# Sch.net
KiCad netlist of a schematic drawn in EAGLE
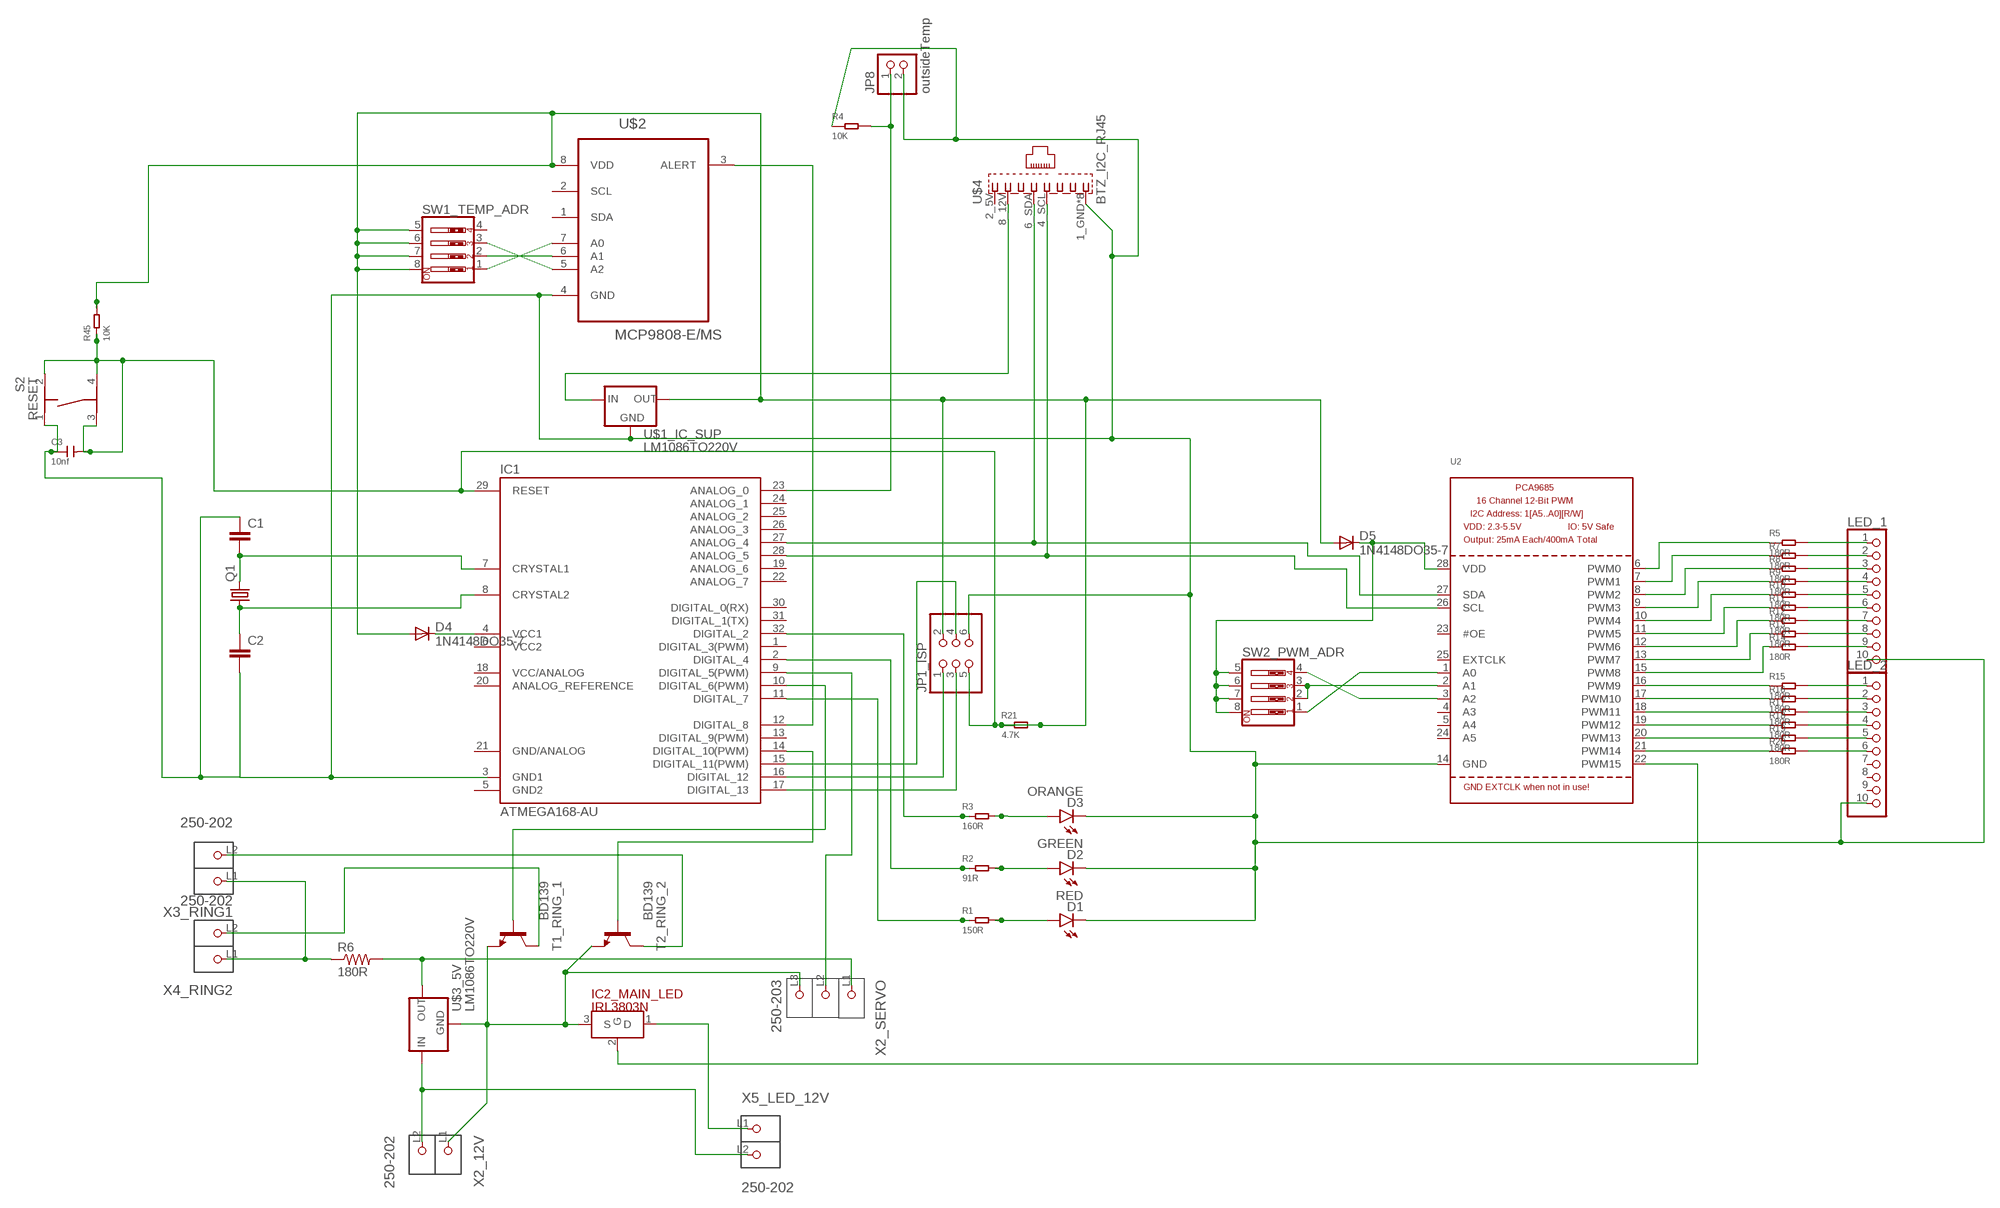
[diagram p0: schematic, sheet 1]

(export (version "E")
  (design (tool "Eeschema 10.0.6"))
  (components
    (comp (ref "C1")
      (value "C-EU025-025X050")
      (footprint "eagle-import:C025-025X050")
      (libsource (lib "eagle-import") (part "C-EU025-025X050"))
    )
    (comp (ref "C2")
      (value "C-EU025-025X050")
      (footprint "eagle-import:C025-025X050")
      (libsource (lib "eagle-import") (part "C-EU025-025X050"))
    )
    (comp (ref "C3")
      (value "10nf")
      (footprint "eagle-import:C0603")
      (fields (field (name "MPN") "CC0603KRX7R9BB103"))
      (libsource (lib "eagle-import") (part "CERAMIC-10NF-50V-10%-X7R(0603)"))
    )
    (comp (ref "D1")
      (value "RED")
      (footprint "eagle-import:LED-0603")
      (libsource (lib "eagle-import") (part "LED-RED0603"))
    )
    (comp (ref "D2")
      (value "GREEN")
      (footprint "eagle-import:LED-0603")
      (libsource (lib "eagle-import") (part "LED-RED0603"))
    )
    (comp (ref "D3")
      (value "ORANGE")
      (footprint "eagle-import:LED-0603")
      (libsource (lib "eagle-import") (part "LED-RED0603"))
    )
    (comp (ref "D4")
      (value "1N4148DO35-7")
      (footprint "eagle-import:DO35-7")
      (libsource (lib "eagle-import") (part "1N4148DO35-7"))
    )
    (comp (ref "D5")
      (value "1N4148DO35-7")
      (footprint "eagle-import:DO35-7")
      (libsource (lib "eagle-import") (part "1N4148DO35-7"))
    )
    (comp (ref "IC1")
      (value "ATMEGA168-AU")
      (footprint "eagle-import:TQFP32-08")
      (libsource (lib "eagle-import") (part "ATMEGA168-AU"))
    )
    (comp (ref "IC2_MAIN_LED")
      (value "IRL3803N")
      (footprint "eagle-import:TO220")
      (libsource (lib "eagle-import") (part "IRL3803N"))
    )
    (comp (ref "JP1_ISP")
      (value "PINHD-2X3")
      (footprint "eagle-import:2X03")
      (libsource (lib "eagle-import") (part "PINHD-2X3"))
    )
    (comp (ref "JP8")
      (value "outsideTemp")
      (footprint "eagle-import:1X02")
      (libsource (lib "eagle-import") (part "PINHD-1X2"))
    )
    (comp (ref "LED_1")
      (value "PINHD-1X10")
      (footprint "eagle-import:1X10")
      (libsource (lib "eagle-import") (part "PINHD-1X10"))
    )
    (comp (ref "LED_2")
      (value "PINHD-1X10")
      (footprint "eagle-import:1X10")
      (libsource (lib "eagle-import") (part "PINHD-1X10"))
    )
    (comp (ref "Q1")
      (value "CRYSTALHC49S")
      (footprint "eagle-import:HC49_S")
      (libsource (lib "eagle-import") (part "CRYSTALHC49S"))
    )
    (comp (ref "R1")
      (value "150R")
      (footprint "eagle-import:R0603")
      (fields (field (name "MPN") "RC0603JR-07100RL"))
      (libsource (lib "eagle-import") (part "SMD-RES-100R-5%-1/10W(0603)"))
    )
    (comp (ref "R2")
      (value "91R")
      (footprint "eagle-import:R0603")
      (fields (field (name "MPN") "RC0603JR-07100RL"))
      (libsource (lib "eagle-import") (part "SMD-RES-100R-5%-1/10W(0603)"))
    )
    (comp (ref "R3")
      (value "160R")
      (footprint "eagle-import:R0603")
      (fields (field (name "MPN") "RC0603JR-07100RL"))
      (libsource (lib "eagle-import") (part "SMD-RES-100R-5%-1/10W(0603)"))
    )
    (comp (ref "R4")
      (value "10K")
      (footprint "eagle-import:R0603")
      (fields (field (name "MPN") "RC0603FR-0710KL"))
      (libsource (lib "eagle-import") (part "SMD-RES-10K-1%-1/10W(0603)"))
    )
    (comp (ref "R5")
      (value "180R")
      (footprint "eagle-import:R0603")
      (fields (field (name "MPN") "RC0603JR-07100RL"))
      (libsource (lib "eagle-import") (part "SMD-RES-100R-5%-1/10W(0603)"))
    )
    (comp (ref "R6")
      (value "180R")
      (footprint "eagle-import:0805-THM")
      (libsource (lib "eagle-import") (part "FLIPFLOP-RES"))
    )
    (comp (ref "R7")
      (value "180R")
      (footprint "eagle-import:R0603")
      (fields (field (name "MPN") "RC0603JR-07100RL"))
      (libsource (lib "eagle-import") (part "SMD-RES-100R-5%-1/10W(0603)"))
    )
    (comp (ref "R8")
      (value "180R")
      (footprint "eagle-import:R0603")
      (fields (field (name "MPN") "RC0603JR-07100RL"))
      (libsource (lib "eagle-import") (part "SMD-RES-100R-5%-1/10W(0603)"))
    )
    (comp (ref "R9")
      (value "180R")
      (footprint "eagle-import:R0603")
      (fields (field (name "MPN") "RC0603JR-07100RL"))
      (libsource (lib "eagle-import") (part "SMD-RES-100R-5%-1/10W(0603)"))
    )
    (comp (ref "R10")
      (value "180R")
      (footprint "eagle-import:R0603")
      (fields (field (name "MPN") "RC0603JR-07100RL"))
      (libsource (lib "eagle-import") (part "SMD-RES-100R-5%-1/10W(0603)"))
    )
    (comp (ref "R11")
      (value "180R")
      (footprint "eagle-import:R0603")
      (fields (field (name "MPN") "RC0603JR-07100RL"))
      (libsource (lib "eagle-import") (part "SMD-RES-100R-5%-1/10W(0603)"))
    )
    (comp (ref "R12")
      (value "180R")
      (footprint "eagle-import:R0603")
      (fields (field (name "MPN") "RC0603JR-07100RL"))
      (libsource (lib "eagle-import") (part "SMD-RES-100R-5%-1/10W(0603)"))
    )
    (comp (ref "R13")
      (value "180R")
      (footprint "eagle-import:R0603")
      (fields (field (name "MPN") "RC0603JR-07100RL"))
      (libsource (lib "eagle-import") (part "SMD-RES-100R-5%-1/10W(0603)"))
    )
    (comp (ref "R14")
      (value "180R")
      (footprint "eagle-import:R0603")
      (fields (field (name "MPN") "RC0603JR-07100RL"))
      (libsource (lib "eagle-import") (part "SMD-RES-100R-5%-1/10W(0603)"))
    )
    (comp (ref "R15")
      (value "180R")
      (footprint "eagle-import:R0603")
      (fields (field (name "MPN") "RC0603JR-07100RL"))
      (libsource (lib "eagle-import") (part "SMD-RES-100R-5%-1/10W(0603)"))
    )
    (comp (ref "R16")
      (value "180R")
      (footprint "eagle-import:R0603")
      (fields (field (name "MPN") "RC0603JR-07100RL"))
      (libsource (lib "eagle-import") (part "SMD-RES-100R-5%-1/10W(0603)"))
    )
    (comp (ref "R17")
      (value "180R")
      (footprint "eagle-import:R0603")
      (fields (field (name "MPN") "RC0603JR-07100RL"))
      (libsource (lib "eagle-import") (part "SMD-RES-100R-5%-1/10W(0603)"))
    )
    (comp (ref "R18")
      (value "180R")
      (footprint "eagle-import:R0603")
      (fields (field (name "MPN") "RC0603JR-07100RL"))
      (libsource (lib "eagle-import") (part "SMD-RES-100R-5%-1/10W(0603)"))
    )
    (comp (ref "R19")
      (value "180R")
      (footprint "eagle-import:R0603")
      (fields (field (name "MPN") "RC0603JR-07100RL"))
      (libsource (lib "eagle-import") (part "SMD-RES-100R-5%-1/10W(0603)"))
    )
    (comp (ref "R20")
      (value "180R")
      (footprint "eagle-import:R0603")
      (fields (field (name "MPN") "RC0603JR-07100RL"))
      (libsource (lib "eagle-import") (part "SMD-RES-100R-5%-1/10W(0603)"))
    )
    (comp (ref "R21")
      (value "4.7K")
      (footprint "eagle-import:R0603")
      (fields (field (name "MPN") "RC0603JR-074K7L"))
      (libsource (lib "eagle-import") (part "SMD-RES-4.7K-5%-1/10W(0603)"))
    )
    (comp (ref "R45")
      (value "10K")
      (footprint "eagle-import:R0603")
      (fields (field (name "MPN") "RC0603FR-0710KL"))
      (libsource (lib "eagle-import") (part "SMD-RES-10K-1%-1/10W(0603)"))
    )
    (comp (ref "S2")
      (value "RESET")
      (footprint "eagle-import:TASTER-9314_SMD")
      (libsource (lib "eagle-import") (part "TASTER-9314_SMD"))
    )
    (comp (ref "SW1_TEMP_ADR")
      (value "SW_DIP-4")
      (footprint "eagle-import:EDG-04")
      (libsource (lib "eagle-import") (part "SW_DIP-4"))
    )
    (comp (ref "SW2_PWM_ADR")
      (value "SW_DIP-4")
      (footprint "eagle-import:EDG-04")
      (libsource (lib "eagle-import") (part "SW_DIP-4"))
    )
    (comp (ref "T1_RING_1")
      (value "BD139")
      (footprint "eagle-import:TO126")
      (libsource (lib "eagle-import") (part "BD139"))
    )
    (comp (ref "T2_RING_2")
      (value "BD139")
      (footprint "eagle-import:TO126")
      (libsource (lib "eagle-import") (part "BD139"))
    )
    (comp (ref "U$1_IC_SUP")
      (value "LM1086TO220V")
      (footprint "eagle-import:TO220S")
      (libsource (lib "eagle-import") (part "LM1086TO220V"))
    )
    (comp (ref "U$2")
      (value "MCP9808-E/MS")
      (footprint "eagle-import:SOP65P490X110-8N")
      (libsource (lib "eagle-import") (part "MCP9808-E/MS"))
    )
    (comp (ref "U$3_5V")
      (value "LM1086TO220V")
      (footprint "eagle-import:TO220S")
      (libsource (lib "eagle-import") (part "LM1086TO220V"))
    )
    (comp (ref "U$4")
      (value "BTZ_I2C_RJ45")
      (footprint "eagle-import:RJ45")
      (libsource (lib "eagle-import") (part "BTZ_I2C_RJ45"))
    )
    (comp (ref "U2")
      (value "PCA9685")
      (footprint "eagle-import:TSSOP28")
      (libsource (lib "eagle-import") (part "PCA9685"))
    )
    (comp (ref "X2_12V")
      (value "250-202")
      (footprint "eagle-import:P-250-202")
      (libsource (lib "eagle-import") (part "250-202"))
    )
    (comp (ref "X2_SERVO")
      (value "250-203")
      (footprint "eagle-import:P-250-203")
      (libsource (lib "eagle-import") (part "250-203"))
    )
    (comp (ref "X3_RING1")
      (value "250-202")
      (footprint "eagle-import:P-250-202")
      (libsource (lib "eagle-import") (part "250-202"))
    )
    (comp (ref "X4_RING2")
      (value "250-202")
      (footprint "eagle-import:P-250-202")
      (libsource (lib "eagle-import") (part "250-202"))
    )
    (comp (ref "X5_LED_12V")
      (value "250-202")
      (footprint "eagle-import:P-250-202")
      (libsource (lib "eagle-import") (part "250-202"))
    )
  )
  (nets
    (net (code "1") (name "/GND1") (class "Default")
      (node (ref "IC1") (pin "3") (pinfunction "GND1_3") (pintype "power_in"))
    )
    (net (code "2") (name "/GND2") (class "Default")
      (node (ref "IC1") (pin "5") (pinfunction "GND2_5") (pintype "power_in"))
    )
    (net (code "3") (name "/GND{slash}ANALOG") (class "Default")
      (node (ref "IC1") (pin "21") (pinfunction "GND/ANALOG_21") (pintype "power_in"))
    )
    (net (code "4") (name "/VCC2") (class "Default")
      (node (ref "IC1") (pin "6") (pinfunction "VCC2_6") (pintype "power_in"))
    )
    (net (code "5") (name "Net-(D1-PadA)") (class "Default")
      (node (ref "D1") (pin "A") (pinfunction "A_A") (pintype "passive"))
      (node (ref "R1") (pin "2") (pinfunction "2_2") (pintype "passive"))
    )
    (net (code "6") (name "Net-(D2-PadA)") (class "Default")
      (node (ref "D2") (pin "A") (pinfunction "A_A") (pintype "passive"))
      (node (ref "R2") (pin "2") (pinfunction "2_2") (pintype "passive"))
    )
    (net (code "7") (name "Net-(D3-PadA)") (class "Default")
      (node (ref "D3") (pin "A") (pinfunction "A_A") (pintype "passive"))
      (node (ref "R3") (pin "2") (pinfunction "2_2") (pintype "passive"))
    )
    (net (code "8") (name "Net-(IC1-ANALOG_0)") (class "Default")
      (node (ref "IC1") (pin "23") (pinfunction "ANALOG_0_23") (pintype "bidirectional"))
      (node (ref "JP8") (pin "1") (pinfunction "1_1") (pintype "passive"))
      (node (ref "R4") (pin "2") (pinfunction "2_2") (pintype "passive"))
    )
    (net (code "9") (name "Net-(IC1-ANALOG_4)") (class "Default")
      (node (ref "IC1") (pin "27") (pinfunction "ANALOG_4_27") (pintype "bidirectional"))
      (node (ref "U$4") (pin "6_SDA") (pinfunction "SDA_6_SDA") (pintype "passive"))
      (node (ref "U2") (pin "27") (pinfunction "SDA_27") (pintype "bidirectional"))
    )
    (net (code "10") (name "Net-(IC1-ANALOG_5)") (class "Default")
      (node (ref "IC1") (pin "28") (pinfunction "ANALOG_5_28") (pintype "bidirectional"))
      (node (ref "U$4") (pin "4_SCL") (pinfunction "SCL_4_SCL") (pintype "passive"))
      (node (ref "U2") (pin "26") (pinfunction "SCL_26") (pintype "bidirectional"))
    )
    (net (code "11") (name "Net-(IC1-CRYSTAL1)") (class "Default")
      (node (ref "C1") (pin "2") (pinfunction "2_2") (pintype "passive"))
      (node (ref "IC1") (pin "7") (pinfunction "CRYSTAL1_7") (pintype "bidirectional"))
      (node (ref "Q1") (pin "2") (pinfunction "2_2") (pintype "passive"))
    )
    (net (code "12") (name "Net-(IC1-CRYSTAL2)") (class "Default")
      (node (ref "C2") (pin "1") (pinfunction "1_1") (pintype "passive"))
      (node (ref "IC1") (pin "8") (pinfunction "CRYSTAL2_8") (pintype "bidirectional"))
      (node (ref "Q1") (pin "1") (pinfunction "1_1") (pintype "passive"))
    )
    (net (code "13") (name "Net-(IC1-DIGITAL_2)") (class "Default")
      (node (ref "IC1") (pin "32") (pinfunction "DIGITAL_2_32") (pintype "bidirectional"))
      (node (ref "R3") (pin "1") (pinfunction "1_1") (pintype "passive"))
    )
    (net (code "14") (name "Net-(IC1-DIGITAL_4)") (class "Default")
      (node (ref "IC1") (pin "2") (pinfunction "DIGITAL_4_2") (pintype "bidirectional"))
      (node (ref "R2") (pin "1") (pinfunction "1_1") (pintype "passive"))
    )
    (net (code "15") (name "Net-(IC1-DIGITAL_5(PWM))") (class "Default")
      (node (ref "IC1") (pin "9") (pinfunction "DIGITAL_5(PWM)_9") (pintype "bidirectional"))
      (node (ref "X2_SERVO") (pin "L2") (pinfunction "P2_L2") (pintype "bidirectional"))
    )
    (net (code "16") (name "Net-(IC1-DIGITAL_6(PWM))") (class "Default")
      (node (ref "IC1") (pin "10") (pinfunction "DIGITAL_6(PWM)_10") (pintype "bidirectional"))
      (node (ref "T1_RING_1") (pin "3") (pinfunction "B_3") (pintype "passive"))
    )
    (net (code "17") (name "Net-(IC1-DIGITAL_7)") (class "Default")
      (node (ref "IC1") (pin "11") (pinfunction "DIGITAL_7_11") (pintype "bidirectional"))
      (node (ref "R1") (pin "1") (pinfunction "1_1") (pintype "passive"))
    )
    (net (code "18") (name "Net-(IC1-DIGITAL_8)") (class "Default")
      (node (ref "IC1") (pin "12") (pinfunction "DIGITAL_8_12") (pintype "bidirectional"))
      (node (ref "U$2") (pin "3") (pinfunction "ALERT_3") (pintype "output"))
    )
    (net (code "19") (name "Net-(IC1-DIGITAL_10(PWM))") (class "Default")
      (node (ref "IC1") (pin "14") (pinfunction "DIGITAL_10(PWM)_14") (pintype "bidirectional"))
      (node (ref "T2_RING_2") (pin "3") (pinfunction "B_3") (pintype "passive"))
    )
    (net (code "20") (name "Net-(IC1-DIGITAL_11(PWM))") (class "Default")
      (node (ref "IC1") (pin "15") (pinfunction "DIGITAL_11(PWM)_15") (pintype "bidirectional"))
      (node (ref "JP1_ISP") (pin "4") (pinfunction "4_4") (pintype "passive"))
    )
    (net (code "21") (name "Net-(IC1-DIGITAL_12)") (class "Default")
      (node (ref "IC1") (pin "16") (pinfunction "DIGITAL_12_16") (pintype "bidirectional"))
      (node (ref "JP1_ISP") (pin "1") (pinfunction "1_1") (pintype "passive"))
    )
    (net (code "22") (name "Net-(IC1-DIGITAL_13)") (class "Default")
      (node (ref "IC1") (pin "17") (pinfunction "DIGITAL_13_17") (pintype "bidirectional"))
      (node (ref "JP1_ISP") (pin "3") (pinfunction "3_3") (pintype "passive"))
    )
    (net (code "23") (name "Net-(IC1-RESET)") (class "Default")
      (node (ref "C3") (pin "2") (pinfunction "2_2") (pintype "passive"))
      (node (ref "D4") (pin "A") (pinfunction "A_A") (pintype "passive"))
      (node (ref "D5") (pin "A") (pinfunction "A_A") (pintype "passive"))
      (node (ref "IC1") (pin "29") (pinfunction "RESET_29") (pintype "bidirectional"))
      (node (ref "JP1_ISP") (pin "2") (pinfunction "2_2") (pintype "passive"))
      (node (ref "JP1_ISP") (pin "5") (pinfunction "5_5") (pintype "passive"))
      (node (ref "R21") (pin "1") (pinfunction "1_1") (pintype "passive"))
      (node (ref "R21") (pin "2") (pinfunction "2_2") (pintype "passive"))
      (node (ref "R45") (pin "1") (pinfunction "1_1") (pintype "passive"))
      (node (ref "R45") (pin "2") (pinfunction "2_2") (pintype "passive"))
      (node (ref "S2") (pin "2") (pinfunction "2_2") (pintype "passive"))
      (node (ref "S2") (pin "3") (pinfunction "3_3") (pintype "passive"))
      (node (ref "S2") (pin "4") (pinfunction "4_4") (pintype "passive"))
      (node (ref "SW1_TEMP_ADR") (pin "5") (pinfunction "5_5") (pintype "passive"))
      (node (ref "SW1_TEMP_ADR") (pin "6") (pinfunction "6_6") (pintype "passive"))
      (node (ref "SW1_TEMP_ADR") (pin "7") (pinfunction "7_7") (pintype "passive"))
      (node (ref "SW1_TEMP_ADR") (pin "8") (pinfunction "8_8") (pintype "passive"))
      (node (ref "U$1_IC_SUP") (pin "2") (pinfunction "OUT_2") (pintype "passive"))
      (node (ref "U$2") (pin "8") (pinfunction "VDD_8") (pintype "power_in"))
    )
    (net (code "24") (name "Net-(IC1-VCC1)") (class "Default")
      (node (ref "D4") (pin "C") (pinfunction "C_C") (pintype "passive"))
      (node (ref "IC1") (pin "4") (pinfunction "VCC1_4") (pintype "power_in"))
    )
    (net (code "25") (name "Net-(IC2_MAIN_LED-D)") (class "Default")
      (node (ref "IC2_MAIN_LED") (pin "1") (pinfunction "D_1") (pintype "output"))
      (node (ref "X5_LED_12V") (pin "L1") (pinfunction "P1_L1") (pintype "bidirectional"))
    )
    (net (code "26") (name "Net-(IC2_MAIN_LED-G)") (class "Default")
      (node (ref "IC2_MAIN_LED") (pin "2") (pinfunction "G_2") (pintype "input"))
      (node (ref "U2") (pin "22") (pinfunction "PWM15_22") (pintype "output"))
    )
    (net (code "27") (name "Net-(IC2_MAIN_LED-S)") (class "Default")
      (node (ref "IC2_MAIN_LED") (pin "3") (pinfunction "S_3") (pintype "power_in"))
      (node (ref "T1_RING_1") (pin "1") (pinfunction "E_1") (pintype "passive"))
      (node (ref "T2_RING_2") (pin "1") (pinfunction "E_1") (pintype "passive"))
      (node (ref "U$3_5V") (pin "1") (pinfunction "GND_1") (pintype "input"))
      (node (ref "X2_12V") (pin "L1") (pinfunction "P1_L1") (pintype "bidirectional"))
      (node (ref "X2_SERVO") (pin "L3") (pinfunction "P3_L3") (pintype "bidirectional"))
    )
    (net (code "28") (name "Net-(LED_1-Pad1)") (class "Default")
      (node (ref "LED_1") (pin "1") (pinfunction "1_1") (pintype "passive"))
      (node (ref "R5") (pin "2") (pinfunction "2_2") (pintype "passive"))
    )
    (net (code "29") (name "Net-(LED_1-Pad2)") (class "Default")
      (node (ref "LED_1") (pin "2") (pinfunction "2_2") (pintype "passive"))
      (node (ref "R7") (pin "2") (pinfunction "2_2") (pintype "passive"))
    )
    (net (code "30") (name "Net-(LED_1-Pad3)") (class "Default")
      (node (ref "LED_1") (pin "3") (pinfunction "3_3") (pintype "passive"))
      (node (ref "R8") (pin "2") (pinfunction "2_2") (pintype "passive"))
    )
    (net (code "31") (name "Net-(LED_1-Pad4)") (class "Default")
      (node (ref "LED_1") (pin "4") (pinfunction "4_4") (pintype "passive"))
      (node (ref "R9") (pin "2") (pinfunction "2_2") (pintype "passive"))
    )
    (net (code "32") (name "Net-(LED_1-Pad5)") (class "Default")
      (node (ref "LED_1") (pin "5") (pinfunction "5_5") (pintype "passive"))
      (node (ref "R10") (pin "2") (pinfunction "2_2") (pintype "passive"))
    )
    (net (code "33") (name "Net-(LED_1-Pad6)") (class "Default")
      (node (ref "LED_1") (pin "6") (pinfunction "6_6") (pintype "passive"))
      (node (ref "R11") (pin "2") (pinfunction "2_2") (pintype "passive"))
    )
    (net (code "34") (name "Net-(LED_1-Pad7)") (class "Default")
      (node (ref "LED_1") (pin "7") (pinfunction "7_7") (pintype "passive"))
      (node (ref "R12") (pin "2") (pinfunction "2_2") (pintype "passive"))
    )
    (net (code "35") (name "Net-(LED_1-Pad8)") (class "Default")
      (node (ref "LED_1") (pin "8") (pinfunction "8_8") (pintype "passive"))
      (node (ref "R13") (pin "2") (pinfunction "2_2") (pintype "passive"))
    )
    (net (code "36") (name "Net-(LED_1-Pad9)") (class "Default")
      (node (ref "LED_1") (pin "9") (pinfunction "9_9") (pintype "passive"))
      (node (ref "R14") (pin "2") (pinfunction "2_2") (pintype "passive"))
    )
    (net (code "37") (name "Net-(LED_2-Pad1)") (class "Default")
      (node (ref "LED_2") (pin "1") (pinfunction "1_1") (pintype "passive"))
      (node (ref "R15") (pin "2") (pinfunction "2_2") (pintype "passive"))
    )
    (net (code "38") (name "Net-(LED_2-Pad2)") (class "Default")
      (node (ref "LED_2") (pin "2") (pinfunction "2_2") (pintype "passive"))
      (node (ref "R16") (pin "2") (pinfunction "2_2") (pintype "passive"))
    )
    (net (code "39") (name "Net-(LED_2-Pad3)") (class "Default")
      (node (ref "LED_2") (pin "3") (pinfunction "3_3") (pintype "passive"))
      (node (ref "R17") (pin "2") (pinfunction "2_2") (pintype "passive"))
    )
    (net (code "40") (name "Net-(LED_2-Pad4)") (class "Default")
      (node (ref "LED_2") (pin "4") (pinfunction "4_4") (pintype "passive"))
      (node (ref "R18") (pin "2") (pinfunction "2_2") (pintype "passive"))
    )
    (net (code "41") (name "Net-(LED_2-Pad5)") (class "Default")
      (node (ref "LED_2") (pin "5") (pinfunction "5_5") (pintype "passive"))
      (node (ref "R19") (pin "2") (pinfunction "2_2") (pintype "passive"))
    )
    (net (code "42") (name "Net-(LED_2-Pad6)") (class "Default")
      (node (ref "LED_2") (pin "6") (pinfunction "6_6") (pintype "passive"))
      (node (ref "R20") (pin "2") (pinfunction "2_2") (pintype "passive"))
    )
    (net (code "43") (name "Net-(T1_RING_1-C)") (class "Default")
      (node (ref "T1_RING_1") (pin "2") (pinfunction "C_2") (pintype "passive"))
      (node (ref "X4_RING2") (pin "L2") (pinfunction "P2_L2") (pintype "bidirectional"))
    )
    (net (code "44") (name "Net-(T2_RING_2-C)") (class "Default")
      (node (ref "T2_RING_2") (pin "2") (pinfunction "C_2") (pintype "passive"))
      (node (ref "X3_RING1") (pin "L2") (pinfunction "P2_L2") (pintype "bidirectional"))
    )
    (net (code "45") (name "Net-(U$1_IC_SUP-GND)") (class "Default")
      (node (ref "C1") (pin "1") (pinfunction "1_1") (pintype "passive"))
      (node (ref "C2") (pin "2") (pinfunction "2_2") (pintype "passive"))
      (node (ref "C3") (pin "1") (pinfunction "1_1") (pintype "passive"))
      (node (ref "D1") (pin "C") (pinfunction "C_C") (pintype "passive"))
      (node (ref "D2") (pin "C") (pinfunction "C_C") (pintype "passive"))
      (node (ref "D3") (pin "C") (pinfunction "C_C") (pintype "passive"))
      (node (ref "JP1_ISP") (pin "6") (pinfunction "6_6") (pintype "passive"))
      (node (ref "JP8") (pin "2") (pinfunction "2_2") (pintype "passive"))
      (node (ref "LED_1") (pin "10") (pinfunction "10_10") (pintype "passive"))
      (node (ref "LED_2") (pin "10") (pinfunction "10_10") (pintype "passive"))
      (node (ref "R4") (pin "1") (pinfunction "1_1") (pintype "passive"))
      (node (ref "S2") (pin "1") (pinfunction "1_1") (pintype "passive"))
      (node (ref "U$1_IC_SUP") (pin "1") (pinfunction "GND_1") (pintype "input"))
      (node (ref "U$2") (pin "4") (pinfunction "GND_4") (pintype "passive"))
      (node (ref "U$4") (pin "1_GND") (pinfunction "GND_1_GND") (pintype "passive"))
      (node (ref "U$4") (pin "3_GND") (pinfunction "GND_3_GND") (pintype "passive"))
      (node (ref "U$4") (pin "5_GND") (pinfunction "GND_5_GND") (pintype "passive"))
      (node (ref "U$4") (pin "7_GND") (pinfunction "GND_7_GND") (pintype "passive"))
      (node (ref "U$4") (pin "G1") (pinfunction "GND_G1") (pintype "passive"))
      (node (ref "U$4") (pin "G2") (pinfunction "GND_G2") (pintype "passive"))
      (node (ref "U$4") (pin "G3") (pinfunction "GND_G3") (pintype "passive"))
      (node (ref "U$4") (pin "G4") (pinfunction "GND_G4") (pintype "passive"))
      (node (ref "U2") (pin "14") (pinfunction "GND_14") (pintype "power_in"))
    )
    (net (code "46") (name "Net-(U$1_IC_SUP-IN)") (class "Default")
      (node (ref "U$1_IC_SUP") (pin "3") (pinfunction "IN_3") (pintype "input"))
      (node (ref "U$4") (pin "8_12V") (pinfunction "12V_8_12V") (pintype "passive"))
    )
    (net (code "47") (name "Net-(U$2-A0)") (class "Default")
      (node (ref "SW1_TEMP_ADR") (pin "1") (pinfunction "1_1") (pintype "passive"))
      (node (ref "U$2") (pin "7") (pinfunction "A0_7") (pintype "input"))
    )
    (net (code "48") (name "Net-(U$2-A1)") (class "Default")
      (node (ref "SW1_TEMP_ADR") (pin "2") (pinfunction "2_2") (pintype "passive"))
      (node (ref "U$2") (pin "6") (pinfunction "A1_6") (pintype "input"))
    )
    (net (code "49") (name "Net-(U$2-A2)") (class "Default")
      (node (ref "SW1_TEMP_ADR") (pin "3") (pinfunction "3_3") (pintype "passive"))
      (node (ref "U$2") (pin "5") (pinfunction "A2_5") (pintype "input"))
    )
    (net (code "50") (name "Net-(U$3_5V-IN)") (class "Default")
      (node (ref "U$3_5V") (pin "3") (pinfunction "IN_3") (pintype "input"))
      (node (ref "X2_12V") (pin "L2") (pinfunction "P2_L2") (pintype "bidirectional"))
      (node (ref "X5_LED_12V") (pin "L2") (pinfunction "P2_L2") (pintype "bidirectional"))
    )
    (net (code "51") (name "Net-(U$3_5V-OUT)") (class "Default")
      (node (ref "R6") (pin "2") (pinfunction "2_2") (pintype "passive"))
      (node (ref "U$3_5V") (pin "2") (pinfunction "OUT_2") (pintype "passive"))
      (node (ref "X2_SERVO") (pin "L1") (pinfunction "P1_L1") (pintype "bidirectional"))
    )
    (net (code "52") (name "Net-(U2-A0)") (class "Default")
      (node (ref "SW2_PWM_ADR") (pin "1") (pinfunction "1_1") (pintype "passive"))
      (node (ref "U2") (pin "1") (pinfunction "A0_1") (pintype "bidirectional"))
    )
    (net (code "53") (name "Net-(U2-A1)") (class "Default")
      (node (ref "SW2_PWM_ADR") (pin "2") (pinfunction "2_2") (pintype "passive"))
      (node (ref "SW2_PWM_ADR") (pin "3") (pinfunction "3_3") (pintype "passive"))
      (node (ref "U2") (pin "2") (pinfunction "A1_2") (pintype "bidirectional"))
    )
    (net (code "54") (name "Net-(U2-A2)") (class "Default")
      (node (ref "SW2_PWM_ADR") (pin "4") (pinfunction "4_4") (pintype "passive"))
      (node (ref "U2") (pin "3") (pinfunction "A2_3") (pintype "bidirectional"))
    )
    (net (code "55") (name "Net-(U2-PWM0)") (class "Default")
      (node (ref "R5") (pin "1") (pinfunction "1_1") (pintype "passive"))
      (node (ref "U2") (pin "6") (pinfunction "PWM0_6") (pintype "output"))
    )
    (net (code "56") (name "Net-(U2-PWM1)") (class "Default")
      (node (ref "R7") (pin "1") (pinfunction "1_1") (pintype "passive"))
      (node (ref "U2") (pin "7") (pinfunction "PWM1_7") (pintype "output"))
    )
    (net (code "57") (name "Net-(U2-PWM2)") (class "Default")
      (node (ref "R8") (pin "1") (pinfunction "1_1") (pintype "passive"))
      (node (ref "U2") (pin "8") (pinfunction "PWM2_8") (pintype "output"))
    )
    (net (code "58") (name "Net-(U2-PWM3)") (class "Default")
      (node (ref "R9") (pin "1") (pinfunction "1_1") (pintype "passive"))
      (node (ref "U2") (pin "9") (pinfunction "PWM3_9") (pintype "output"))
    )
    (net (code "59") (name "Net-(U2-PWM4)") (class "Default")
      (node (ref "R10") (pin "1") (pinfunction "1_1") (pintype "passive"))
      (node (ref "U2") (pin "10") (pinfunction "PWM4_10") (pintype "output"))
    )
    (net (code "60") (name "Net-(U2-PWM5)") (class "Default")
      (node (ref "R11") (pin "1") (pinfunction "1_1") (pintype "passive"))
      (node (ref "U2") (pin "11") (pinfunction "PWM5_11") (pintype "output"))
    )
    (net (code "61") (name "Net-(U2-PWM6)") (class "Default")
      (node (ref "R12") (pin "1") (pinfunction "1_1") (pintype "passive"))
      (node (ref "U2") (pin "12") (pinfunction "PWM6_12") (pintype "output"))
    )
    (net (code "62") (name "Net-(U2-PWM7)") (class "Default")
      (node (ref "R13") (pin "1") (pinfunction "1_1") (pintype "passive"))
      (node (ref "U2") (pin "13") (pinfunction "PWM7_13") (pintype "output"))
    )
    (net (code "63") (name "Net-(U2-PWM8)") (class "Default")
      (node (ref "R14") (pin "1") (pinfunction "1_1") (pintype "passive"))
      (node (ref "U2") (pin "15") (pinfunction "PWM8_15") (pintype "output"))
    )
    (net (code "64") (name "Net-(U2-PWM9)") (class "Default")
      (node (ref "R15") (pin "1") (pinfunction "1_1") (pintype "passive"))
      (node (ref "U2") (pin "16") (pinfunction "PWM9_16") (pintype "output"))
    )
    (net (code "65") (name "Net-(U2-PWM10)") (class "Default")
      (node (ref "R16") (pin "1") (pinfunction "1_1") (pintype "passive"))
      (node (ref "U2") (pin "17") (pinfunction "PWM10_17") (pintype "output"))
    )
    (net (code "66") (name "Net-(U2-PWM11)") (class "Default")
      (node (ref "R17") (pin "1") (pinfunction "1_1") (pintype "passive"))
      (node (ref "U2") (pin "18") (pinfunction "PWM11_18") (pintype "output"))
    )
    (net (code "67") (name "Net-(U2-PWM12)") (class "Default")
      (node (ref "R18") (pin "1") (pinfunction "1_1") (pintype "passive"))
      (node (ref "U2") (pin "19") (pinfunction "PWM12_19") (pintype "output"))
    )
    (net (code "68") (name "Net-(U2-PWM13)") (class "Default")
      (node (ref "R19") (pin "1") (pinfunction "1_1") (pintype "passive"))
      (node (ref "U2") (pin "20") (pinfunction "PWM13_20") (pintype "output"))
    )
    (net (code "69") (name "Net-(U2-PWM14)") (class "Default")
      (node (ref "R20") (pin "1") (pinfunction "1_1") (pintype "passive"))
      (node (ref "U2") (pin "21") (pinfunction "PWM14_21") (pintype "output"))
    )
    (net (code "70") (name "Net-(U2-VDD)") (class "Default")
      (node (ref "D5") (pin "C") (pinfunction "C_C") (pintype "passive"))
      (node (ref "SW2_PWM_ADR") (pin "5") (pinfunction "5_5") (pintype "passive"))
      (node (ref "SW2_PWM_ADR") (pin "6") (pinfunction "6_6") (pintype "passive"))
      (node (ref "SW2_PWM_ADR") (pin "7") (pinfunction "7_7") (pintype "passive"))
      (node (ref "SW2_PWM_ADR") (pin "8") (pinfunction "8_8") (pintype "passive"))
      (node (ref "U2") (pin "28") (pinfunction "VDD_28") (pintype "power_in"))
    )
    (net (code "71") (name "Net-(X3_RING1-P1)") (class "Default")
      (node (ref "R6") (pin "1") (pinfunction "1_1") (pintype "passive"))
      (node (ref "X3_RING1") (pin "L1") (pinfunction "P1_L1") (pintype "bidirectional"))
      (node (ref "X4_RING2") (pin "L1") (pinfunction "P1_L1") (pintype "bidirectional"))
    )
    (net (code "72") (name "unconnected-(IC1-ANALOG_1-Pad24)") (class "Default")
      (node (ref "IC1") (pin "24") (pinfunction "ANALOG_1_24") (pintype "bidirectional"))
    )
    (net (code "73") (name "unconnected-(IC1-ANALOG_2-Pad25)") (class "Default")
      (node (ref "IC1") (pin "25") (pinfunction "ANALOG_2_25") (pintype "bidirectional"))
    )
    (net (code "74") (name "unconnected-(IC1-ANALOG_3-Pad26)") (class "Default")
      (node (ref "IC1") (pin "26") (pinfunction "ANALOG_3_26") (pintype "bidirectional"))
    )
    (net (code "75") (name "unconnected-(IC1-ANALOG_6-Pad19)") (class "Default")
      (node (ref "IC1") (pin "19") (pinfunction "ANALOG_6_19") (pintype "passive"))
    )
    (net (code "76") (name "unconnected-(IC1-ANALOG_7-Pad22)") (class "Default")
      (node (ref "IC1") (pin "22") (pinfunction "ANALOG_7_22") (pintype "passive"))
    )
    (net (code "77") (name "unconnected-(IC1-ANALOG_REFERENCE-Pad20)") (class "Default")
      (node (ref "IC1") (pin "20") (pinfunction "ANALOG_REFERENCE_20") (pintype "passive"))
    )
    (net (code "78") (name "unconnected-(IC1-DIGITAL_0(RX)-Pad30)") (class "Default")
      (node (ref "IC1") (pin "30") (pinfunction "DIGITAL_0(RX)_30") (pintype "bidirectional"))
    )
    (net (code "79") (name "unconnected-(IC1-DIGITAL_1(TX)-Pad31)") (class "Default")
      (node (ref "IC1") (pin "31") (pinfunction "DIGITAL_1(TX)_31") (pintype "bidirectional"))
    )
    (net (code "80") (name "unconnected-(IC1-DIGITAL_3(PWM)-Pad1)") (class "Default")
      (node (ref "IC1") (pin "1") (pinfunction "DIGITAL_3(PWM)_1") (pintype "bidirectional"))
    )
    (net (code "81") (name "unconnected-(IC1-DIGITAL_9(PWM)-Pad13)") (class "Default")
      (node (ref "IC1") (pin "13") (pinfunction "DIGITAL_9(PWM)_13") (pintype "bidirectional"))
    )
    (net (code "82") (name "unconnected-(IC1-VCC{slash}ANALOG-Pad18)") (class "Default")
      (node (ref "IC1") (pin "18") (pinfunction "VCC/ANALOG_18") (pintype "passive"))
    )
    (net (code "83") (name "unconnected-(LED_2-Pad7)") (class "Default")
      (node (ref "LED_2") (pin "7") (pinfunction "7_7") (pintype "passive"))
    )
    (net (code "84") (name "unconnected-(LED_2-Pad8)") (class "Default")
      (node (ref "LED_2") (pin "8") (pinfunction "8_8") (pintype "passive"))
    )
    (net (code "85") (name "unconnected-(LED_2-Pad9)") (class "Default")
      (node (ref "LED_2") (pin "9") (pinfunction "9_9") (pintype "passive"))
    )
    (net (code "86") (name "unconnected-(SW1_TEMP_ADR-Pad4)") (class "Default")
      (node (ref "SW1_TEMP_ADR") (pin "4") (pinfunction "4_4") (pintype "passive"))
    )
    (net (code "87") (name "unconnected-(U$2-SCL-Pad2)") (class "Default")
      (node (ref "U$2") (pin "2") (pinfunction "SCL_2") (pintype "input"))
    )
    (net (code "88") (name "unconnected-(U$2-SDA-Pad1)") (class "Default")
      (node (ref "U$2") (pin "1") (pinfunction "SDA_1") (pintype "bidirectional"))
    )
    (net (code "89") (name "unconnected-(U$4-5V-Pad2_5V)") (class "Default")
      (node (ref "U$4") (pin "2_5V") (pinfunction "5V_2_5V") (pintype "passive"))
    )
    (net (code "90") (name "unconnected-(U2-#OE-Pad23)") (class "Default")
      (node (ref "U2") (pin "23") (pinfunction "#OE_23") (pintype "input"))
    )
    (net (code "91") (name "unconnected-(U2-A3-Pad4)") (class "Default")
      (node (ref "U2") (pin "4") (pinfunction "A3_4") (pintype "bidirectional"))
    )
    (net (code "92") (name "unconnected-(U2-A4-Pad5)") (class "Default")
      (node (ref "U2") (pin "5") (pinfunction "A4_5") (pintype "bidirectional"))
    )
    (net (code "93") (name "unconnected-(U2-A5-Pad24)") (class "Default")
      (node (ref "U2") (pin "24") (pinfunction "A5_24") (pintype "bidirectional"))
    )
    (net (code "94") (name "unconnected-(U2-EXTCLK-Pad25)") (class "Default")
      (node (ref "U2") (pin "25") (pinfunction "EXTCLK_25") (pintype "input"))
    )
  )
)
